# EC-Remoter.net
KiCad netlist of a schematic drawn in Altium Designer
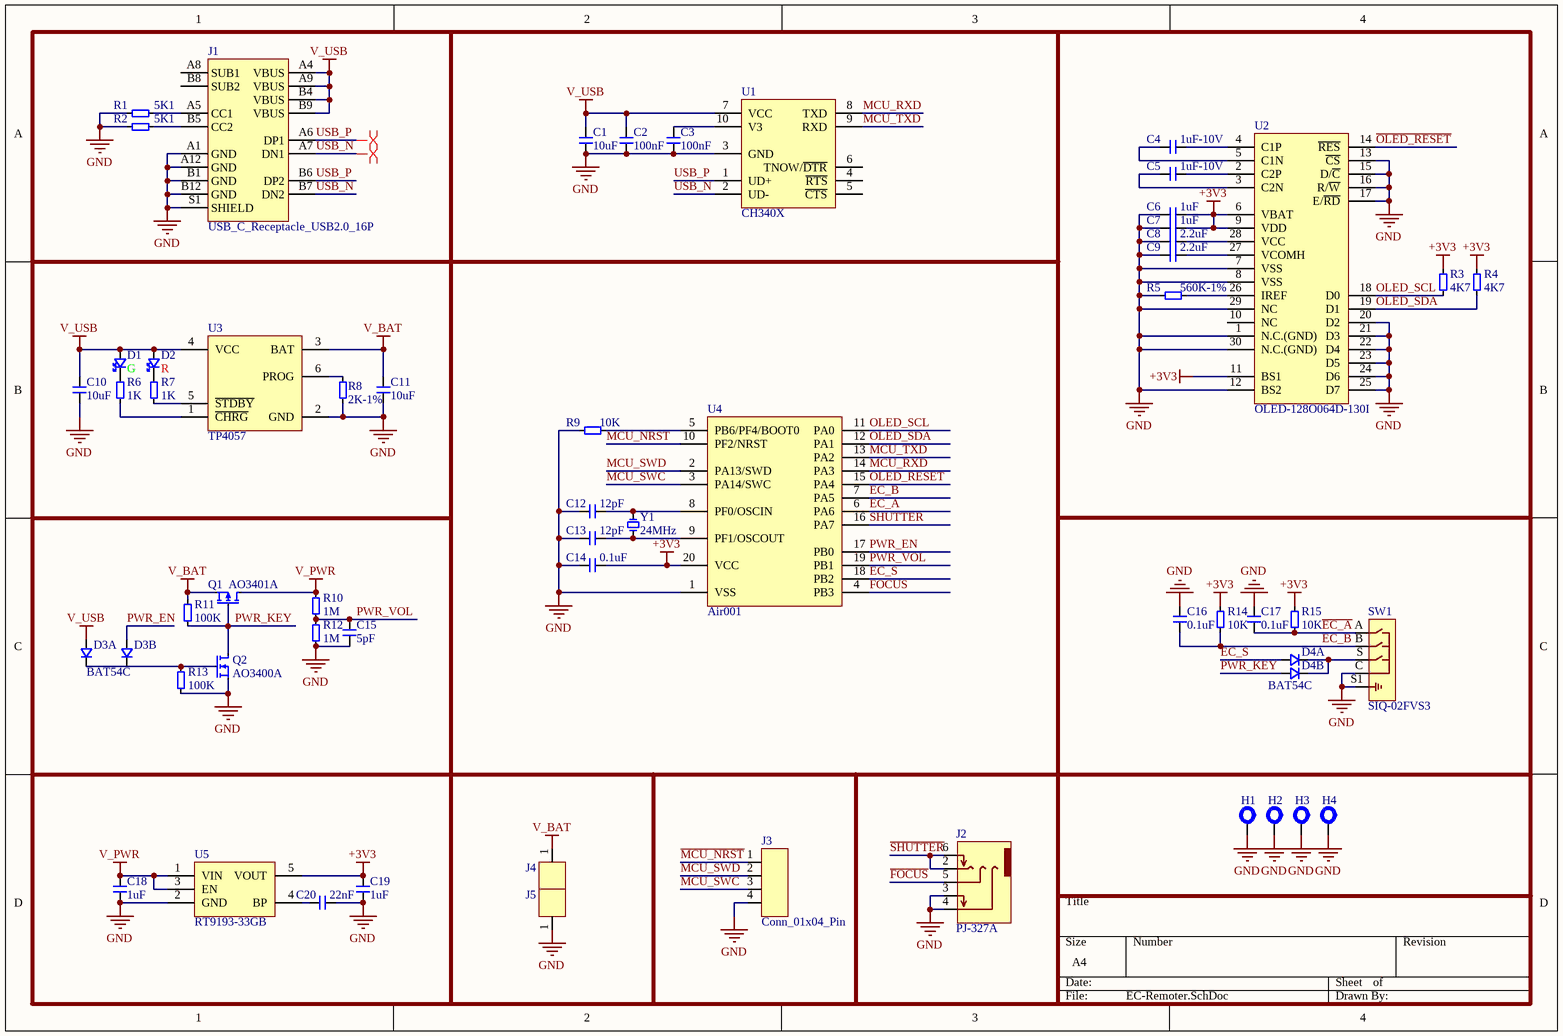
[diagram p0: EC-Remoter.SchDoc]

(export (version "E")
  (design (tool "Eeschema 10.0.6"))
  (components
    (comp (ref "C1")
      (value "10uF")
      (footprint "C_0402_1005Metric")
      (description "Capacitor")
      (libsource (lib "xu-yingjing") (part "C"))
    )
    (comp (ref "C2")
      (value "100nF")
      (footprint "C_0402_1005Metric")
      (description "Capacitor")
      (libsource (lib "xu-yingjing") (part "C"))
    )
    (comp (ref "C3")
      (value "100nF")
      (footprint "C_0402_1005Metric")
      (description "Capacitor")
      (libsource (lib "xu-yingjing") (part "C"))
    )
    (comp (ref "C4")
      (value "1uF-10V")
      (footprint "C_0402_1005Metric")
      (description "Capacitor")
      (libsource (lib "xu-yingjing") (part "C"))
    )
    (comp (ref "C5")
      (value "1uF-10V")
      (footprint "C_0402_1005Metric")
      (description "Capacitor")
      (libsource (lib "xu-yingjing") (part "C"))
    )
    (comp (ref "C6")
      (value "1uF")
      (footprint "C_0402_1005Metric")
      (description "Capacitor")
      (libsource (lib "xu-yingjing") (part "C"))
    )
    (comp (ref "C7")
      (value "1uF")
      (footprint "C_0402_1005Metric")
      (description "Capacitor")
      (libsource (lib "xu-yingjing") (part "C"))
    )
    (comp (ref "C8")
      (value "2.2uF")
      (footprint "C_0402_1005Metric")
      (description "Capacitor")
      (libsource (lib "xu-yingjing") (part "C"))
    )
    (comp (ref "C9")
      (value "2.2uF")
      (footprint "C_0402_1005Metric")
      (description "Capacitor")
      (libsource (lib "xu-yingjing") (part "C"))
    )
    (comp (ref "C10")
      (value "10uF")
      (footprint "C_0402_1005Metric")
      (description "Capacitor")
      (libsource (lib "xu-yingjing") (part "C"))
    )
    (comp (ref "C11")
      (value "10uF")
      (footprint "C_0402_1005Metric")
      (description "Capacitor")
      (libsource (lib "xu-yingjing") (part "C"))
    )
    (comp (ref "C12")
      (value "12pF")
      (footprint "C_0402_1005Metric")
      (description "Capacitor")
      (libsource (lib "xu-yingjing") (part "C"))
    )
    (comp (ref "C13")
      (value "12pF")
      (footprint "C_0402_1005Metric")
      (description "Capacitor")
      (libsource (lib "xu-yingjing") (part "C"))
    )
    (comp (ref "C14")
      (value "0.1uF")
      (footprint "C_0402_1005Metric")
      (description "Capacitor")
      (libsource (lib "xu-yingjing") (part "C"))
    )
    (comp (ref "C15")
      (value "5pF")
      (footprint "C_0402_1005Metric")
      (description "Capacitor")
      (libsource (lib "xu-yingjing") (part "C"))
    )
    (comp (ref "C16")
      (value "0.1uF")
      (footprint "C_0402_1005Metric")
      (description "Capacitor")
      (libsource (lib "xu-yingjing") (part "C"))
    )
    (comp (ref "C17")
      (value "0.1uF")
      (footprint "C_0402_1005Metric")
      (description "Capacitor")
      (libsource (lib "xu-yingjing") (part "C"))
    )
    (comp (ref "C18")
      (value "1uF")
      (footprint "C_0402_1005Metric")
      (description "Capacitor")
      (libsource (lib "xu-yingjing") (part "C"))
    )
    (comp (ref "C19")
      (value "1uF")
      (footprint "C_0402_1005Metric")
      (description "Capacitor")
      (libsource (lib "xu-yingjing") (part "C"))
    )
    (comp (ref "C20")
      (value "22nF")
      (footprint "C_0402_1005Metric")
      (description "Capacitor")
      (libsource (lib "xu-yingjing") (part "C"))
    )
    (comp (ref "D1")
      (value "G")
      (footprint "LED_0603_1608Metric")
      (description "Light emitting diode")
      (libsource (lib "xu-yingjing") (part "LED"))
    )
    (comp (ref "D2")
      (value "R")
      (footprint "LED_0603_1608Metric")
      (description "Light emitting diode")
      (libsource (lib "xu-yingjing") (part "LED"))
    )
    (comp (ref "D3")
      (value "BAT54C")
      (footprint "SOT-23-3")
      (description "dual schottky barrier diode, common cathode")
      (libsource (lib "xu-yingjing") (part "BAT54C"))
    )
    (comp (ref "D4")
      (value "BAT54C")
      (footprint "SOT-23-3")
      (description "dual schottky barrier diode, common cathode")
      (libsource (lib "xu-yingjing") (part "BAT54C"))
    )
    (comp (ref "H1")
      (value "MountingHole_Pad")
      (footprint "MountingHole_2.2mm_M2_Pad_Via")
      (description "Mounting Hole with connection")
      (libsource (lib "xu-yingjing") (part "MountingHole_Pad"))
    )
    (comp (ref "H2")
      (value "MountingHole_Pad")
      (footprint "MountingHole_2.2mm_M2_Pad_Via")
      (description "Mounting Hole with connection")
      (libsource (lib "xu-yingjing") (part "MountingHole_Pad"))
    )
    (comp (ref "H3")
      (value "MountingHole_Pad")
      (footprint "MountingHole_2.2mm_M2_Pad_Via")
      (description "Mounting Hole with connection")
      (libsource (lib "xu-yingjing") (part "MountingHole_Pad"))
    )
    (comp (ref "H4")
      (value "MountingHole_Pad")
      (footprint "MountingHole_2.2mm_M2_Pad_Via")
      (description "Mounting Hole with connection")
      (libsource (lib "xu-yingjing") (part "MountingHole_Pad"))
    )
    (comp (ref "J1")
      (value "USB_C_Receptacle_USB2.0_16P")
      (footprint "USB_C_Receptacle_GCT_USB4105-xx-A_16P_TopMnt_Horizontal")
      (description "USB 2.0-only 16P Type-C Receptacle connector")
      (libsource (lib "xu-yingjing") (part "USB_C_Receptacle_USB2.0_16P"))
    )
    (comp (ref "J2")
      (value "PJ-327A")
      (footprint "Jack_3.5mm_PJ327A_Horizontal")
      (libsource (lib "xu-yingjing") (part "PJ-327A"))
    )
    (comp (ref "J3")
      (value "Conn_01x04_Pin")
      (footprint "PinHeader_1x04_P2.54mm_Vertical")
      (description "Generic connector, single row, 01x04")
      (libsource (lib "xu-yingjing") (part "Conn_01x04_Pin"))
    )
    (comp (ref "J4")
      (value "Conn_01x01_Pin")
      (footprint "TestPoint_Plated_Hole_D1.0mm")
      (description "Generic connector, single row, 01x01")
      (libsource (lib "") (part "Conn_01x01_Pin_1"))
    )
    (comp (ref "J5")
      (value "Conn_01x01_Pin")
      (footprint "TestPoint_Plated_Hole_D1.0mm")
      (description "Generic connector, single row, 01x01")
      (libsource (lib "xu-yingjing") (part "Conn_01x01_Pin"))
    )
    (comp (ref "Q1")
      (value "AO3401A")
      (footprint "SOT-23-3")
      (description "Package_TO_SOT_SMD:SOT-23")
      (libsource (lib "xu-yingjing") (part "AO3401A"))
    )
    (comp (ref "Q2")
      (value "AO3400A")
      (footprint "SOT-23-3")
      (description "30V Vds, 5.7A Id, N-Channel MOSFET, SOT-23")
      (libsource (lib "xu-yingjing") (part "AO3400A"))
    )
    (comp (ref "R1")
      (value "5K1")
      (footprint "R_0402_1005Metric")
      (description "Resistor")
      (libsource (lib "xu-yingjing") (part "R"))
    )
    (comp (ref "R2")
      (value "5K1")
      (footprint "R_0402_1005Metric")
      (description "Resistor")
      (libsource (lib "xu-yingjing") (part "R"))
    )
    (comp (ref "R3")
      (value "4K7")
      (footprint "R_0402_1005Metric")
      (description "Resistor")
      (libsource (lib "xu-yingjing") (part "R"))
    )
    (comp (ref "R4")
      (value "4K7")
      (footprint "R_0402_1005Metric")
      (description "Resistor")
      (libsource (lib "xu-yingjing") (part "R"))
    )
    (comp (ref "R5")
      (value "560K-1%")
      (footprint "R_0402_1005Metric")
      (description "Resistor")
      (libsource (lib "xu-yingjing") (part "R"))
    )
    (comp (ref "R6")
      (value "1K")
      (footprint "R_0402_1005Metric")
      (description "Resistor")
      (libsource (lib "xu-yingjing") (part "R"))
    )
    (comp (ref "R7")
      (value "1K")
      (footprint "R_0402_1005Metric")
      (description "Resistor")
      (libsource (lib "xu-yingjing") (part "R"))
    )
    (comp (ref "R8")
      (value "2K-1%")
      (footprint "R_0402_1005Metric")
      (description "Resistor")
      (libsource (lib "xu-yingjing") (part "R"))
    )
    (comp (ref "R9")
      (value "10K")
      (footprint "R_0402_1005Metric")
      (description "Resistor")
      (libsource (lib "xu-yingjing") (part "R"))
    )
    (comp (ref "R10")
      (value "1M")
      (footprint "R_0402_1005Metric")
      (description "Resistor")
      (libsource (lib "xu-yingjing") (part "R"))
    )
    (comp (ref "R11")
      (value "100K")
      (footprint "R_0402_1005Metric")
      (description "Resistor")
      (libsource (lib "xu-yingjing") (part "R"))
    )
    (comp (ref "R12")
      (value "1M")
      (footprint "R_0402_1005Metric")
      (description "Resistor")
      (libsource (lib "xu-yingjing") (part "R"))
    )
    (comp (ref "R13")
      (value "100K")
      (footprint "R_0402_1005Metric")
      (description "Resistor")
      (libsource (lib "xu-yingjing") (part "R"))
    )
    (comp (ref "R14")
      (value "10K")
      (footprint "R_0402_1005Metric")
      (description "Resistor")
      (libsource (lib "xu-yingjing") (part "R"))
    )
    (comp (ref "R15")
      (value "10K")
      (footprint "R_0402_1005Metric")
      (description "Resistor")
      (libsource (lib "xu-yingjing") (part "R"))
    )
    (comp (ref "SW1")
      (value "SIQ-02FVS3")
      (footprint "SIQ-02FVS3")
      (libsource (lib "xu-yingjing") (part "SIQ-02FVS3"))
    )
    (comp (ref "U1")
      (value "CH340X")
      (footprint "MSOP-10_3x3mm_P0.5mm")
      (description "USB serial converter, 5V-tolerant IO, UART, MSOP-10")
      (libsource (lib "xu-yingjing") (part "CH340X"))
    )
    (comp (ref "U2")
      (value "OLED-128O064D-130I")
      (footprint "OLED-128O064D")
      (description "1.30' OLED display 128x64")
      (libsource (lib "xu-yingjing") (part "OLED-128O064D-130I"))
    )
    (comp (ref "U3")
      (value "TP4057")
      (footprint "SOT-23-6")
      (description "500mA Single-Cell Li-Ion Charger, SOT-23-6")
      (libsource (lib "xu-yingjing") (part "TP4057"))
    )
    (comp (ref "U4")
      (value "Air001")
      (footprint "TSSOP-20_4.4x6.5mm_P0.65mm")
      (description "合宙 Arm Cortex-M0+ MCU, 32KB Flash, 4KB RAM, 48 MHz, 1.7-5.5V, 18 GPIO, TSSOP20")
      (libsource (lib "xu-yingjing") (part "Air001"))
    )
    (comp (ref "U5")
      (value "RT9193-33GB")
      (footprint "SOT-23-5")
      (description "Positive 300mA Low Dropout Regulator")
      (libsource (lib "xu-yingjing") (part "RT9193"))
    )
    (comp (ref "Y1")
      (value "24MHz")
      (footprint "Crystal_SMD_3225-4Pin_3.2x2.5mm")
      (description "Crystal")
      (libsource (lib "xu-yingjing") (part "Crystal"))
    )
  )
  (nets
    (net (code "1") (name "+3V3") (class "Default")
      (node (ref "C14") (pin "2") (pinfunction "2_2") (pintype "passive"))
      (node (ref "C19") (pin "1") (pinfunction "1_1") (pintype "passive"))
      (node (ref "C6") (pin "2") (pinfunction "2_2") (pintype "passive"))
      (node (ref "C7") (pin "2") (pinfunction "2_2") (pintype "passive"))
      (node (ref "R14") (pin "2") (pinfunction "2_2") (pintype "passive"))
      (node (ref "R15") (pin "2") (pinfunction "2_2") (pintype "passive"))
      (node (ref "R3") (pin "1") (pinfunction "1_1") (pintype "passive"))
      (node (ref "R4") (pin "1") (pinfunction "1_1") (pintype "passive"))
      (node (ref "U2") (pin "11") (pinfunction "BS1_11") (pintype "passive"))
      (node (ref "U2") (pin "6") (pinfunction "VBAT_6") (pintype "passive"))
      (node (ref "U2") (pin "9") (pinfunction "VDD_9") (pintype "passive"))
      (node (ref "U4") (pin "20") (pinfunction "VCC_20") (pintype "passive"))
      (node (ref "U5") (pin "5") (pinfunction "VOUT_5") (pintype "passive"))
    )
    (net (code "2") (name "/MCU_RXD") (class "Default")
      (node (ref "U1") (pin "8") (pinfunction "TXD_8") (pintype "passive"))
      (node (ref "U4") (pin "14") (pinfunction "PA3_14") (pintype "passive"))
    )
    (net (code "3") (name "/MCU_SWC") (class "Default")
      (node (ref "J3") (pin "3") (pinfunction "3_3") (pintype "passive"))
      (node (ref "U4") (pin "3") (pinfunction "PA14/SWC_3") (pintype "passive"))
    )
    (net (code "4") (name "/MCU_SWD") (class "Default")
      (node (ref "J3") (pin "2") (pinfunction "2_2") (pintype "passive"))
      (node (ref "U4") (pin "2") (pinfunction "PA13/SWD_2") (pintype "passive"))
    )
    (net (code "5") (name "/MCU_TXD") (class "Default")
      (node (ref "U1") (pin "9") (pinfunction "RXD_9") (pintype "passive"))
      (node (ref "U4") (pin "13") (pinfunction "PA2_13") (pintype "passive"))
    )
    (net (code "6") (name "/OLED_SCL") (class "Default")
      (node (ref "R3") (pin "2") (pinfunction "2_2") (pintype "passive"))
      (node (ref "U2") (pin "18") (pinfunction "D0_18") (pintype "passive"))
      (node (ref "U4") (pin "11") (pinfunction "PA0_11") (pintype "passive"))
    )
    (net (code "7") (name "/OLED_SDA") (class "Default")
      (node (ref "R4") (pin "2") (pinfunction "2_2") (pintype "passive"))
      (node (ref "U2") (pin "19") (pinfunction "D1_19") (pintype "passive"))
      (node (ref "U4") (pin "12") (pinfunction "PA1_12") (pintype "passive"))
    )
    (net (code "8") (name "/PWR_EN") (class "Default")
      (node (ref "D3") (pin "2") (pinfunction "2_2") (pintype "passive"))
      (node (ref "U4") (pin "17") (pinfunction "PB0_17") (pintype "passive"))
    )
    (net (code "9") (name "/PWR_KEY") (class "Default")
      (node (ref "D4") (pin "2") (pinfunction "2_2") (pintype "passive"))
      (node (ref "Q1") (pin "1") (pinfunction "G_1") (pintype "passive"))
      (node (ref "Q2") (pin "3") (pinfunction "D_3") (pintype "passive"))
      (node (ref "R11") (pin "1") (pinfunction "1_1") (pintype "passive"))
    )
    (net (code "10") (name "/PWR_VOL") (class "Default")
      (node (ref "C15") (pin "1") (pinfunction "1_1") (pintype "passive"))
      (node (ref "R10") (pin "2") (pinfunction "2_2") (pintype "passive"))
      (node (ref "R12") (pin "1") (pinfunction "1_1") (pintype "passive"))
      (node (ref "U4") (pin "19") (pinfunction "PB1_19") (pintype "passive"))
    )
    (net (code "11") (name "/USB_N") (class "Default")
      (node (ref "J1") (pin "A7") (pinfunction "DN1_A7") (pintype "passive"))
      (node (ref "J1") (pin "B7") (pinfunction "DN2_B7") (pintype "passive"))
      (node (ref "U1") (pin "2") (pinfunction "UD-_2") (pintype "passive"))
    )
    (net (code "12") (name "/USB_P") (class "Default")
      (node (ref "J1") (pin "A6") (pinfunction "DP1_A6") (pintype "passive"))
      (node (ref "J1") (pin "B6") (pinfunction "DP2_B6") (pintype "passive"))
      (node (ref "U1") (pin "1") (pinfunction "UD+_1") (pintype "passive"))
    )
    (net (code "13") (name "/~{EC_A}") (class "Default")
      (node (ref "C17") (pin "1") (pinfunction "1_1") (pintype "passive"))
      (node (ref "R15") (pin "1") (pinfunction "1_1") (pintype "passive"))
      (node (ref "SW1") (pin "A") (pinfunction "A_A") (pintype "passive"))
      (node (ref "U4") (pin "6") (pinfunction "PA6_6") (pintype "passive"))
    )
    (net (code "14") (name "/~{EC_B}") (class "Default")
      (node (ref "C16") (pin "1") (pinfunction "1_1") (pintype "passive"))
      (node (ref "R14") (pin "1") (pinfunction "1_1") (pintype "passive"))
      (node (ref "SW1") (pin "B") (pinfunction "B_B") (pintype "passive"))
      (node (ref "U4") (pin "7") (pinfunction "PA5_7") (pintype "passive"))
    )
    (net (code "15") (name "/~{EC_S}") (class "Default")
      (node (ref "D4") (pin "1") (pinfunction "1_1") (pintype "passive"))
      (node (ref "U4") (pin "18") (pinfunction "PB2_18") (pintype "passive"))
    )
    (net (code "16") (name "/~{FOCUS}") (class "Default")
      (node (ref "J2") (pin "5") (pinfunction "5_5") (pintype "passive"))
      (node (ref "U4") (pin "4") (pinfunction "PB3_4") (pintype "passive"))
    )
    (net (code "17") (name "/~{MCU_NRST}") (class "Default")
      (node (ref "J3") (pin "1") (pinfunction "1_1") (pintype "passive"))
      (node (ref "U4") (pin "10") (pinfunction "PF2/NRST_10") (pintype "passive"))
    )
    (net (code "18") (name "/~{OLED_RESET}") (class "Default")
      (node (ref "U2") (pin "14") (pinfunction "~{RES}_14") (pintype "passive"))
      (node (ref "U4") (pin "15") (pinfunction "PA4_15") (pintype "passive"))
    )
    (net (code "19") (name "/~{SHUTTER}") (class "Default")
      (node (ref "J2") (pin "2") (pinfunction "2_2") (pintype "passive"))
      (node (ref "J2") (pin "6") (pinfunction "6_6") (pintype "passive"))
      (node (ref "U4") (pin "16") (pinfunction "PA7_16") (pintype "passive"))
    )
    (net (code "20") (name "GND") (class "Default")
      (node (ref "C1") (pin "2") (pinfunction "2_2") (pintype "passive"))
      (node (ref "C10") (pin "2") (pinfunction "2_2") (pintype "passive"))
      (node (ref "C11") (pin "2") (pinfunction "2_2") (pintype "passive"))
      (node (ref "C12") (pin "1") (pinfunction "1_1") (pintype "passive"))
      (node (ref "C13") (pin "1") (pinfunction "1_1") (pintype "passive"))
      (node (ref "C14") (pin "1") (pinfunction "1_1") (pintype "passive"))
      (node (ref "C15") (pin "2") (pinfunction "2_2") (pintype "passive"))
      (node (ref "C16") (pin "2") (pinfunction "2_2") (pintype "passive"))
      (node (ref "C17") (pin "2") (pinfunction "2_2") (pintype "passive"))
      (node (ref "C18") (pin "2") (pinfunction "2_2") (pintype "passive"))
      (node (ref "C19") (pin "2") (pinfunction "2_2") (pintype "passive"))
      (node (ref "C2") (pin "2") (pinfunction "2_2") (pintype "passive"))
      (node (ref "C20") (pin "2") (pinfunction "2_2") (pintype "passive"))
      (node (ref "C3") (pin "2") (pinfunction "2_2") (pintype "passive"))
      (node (ref "C6") (pin "1") (pinfunction "1_1") (pintype "passive"))
      (node (ref "C7") (pin "1") (pinfunction "1_1") (pintype "passive"))
      (node (ref "C8") (pin "1") (pinfunction "1_1") (pintype "passive"))
      (node (ref "C9") (pin "1") (pinfunction "1_1") (pintype "passive"))
      (node (ref "H1") (pin "1") (pinfunction "1_1") (pintype "passive"))
      (node (ref "H2") (pin "1") (pinfunction "1_1") (pintype "passive"))
      (node (ref "H3") (pin "1") (pinfunction "1_1") (pintype "passive"))
      (node (ref "H4") (pin "1") (pinfunction "1_1") (pintype "passive"))
      (node (ref "J1") (pin "A1") (pinfunction "GND_A1") (pintype "passive"))
      (node (ref "J1") (pin "A12") (pinfunction "GND_A12") (pintype "passive"))
      (node (ref "J1") (pin "B1") (pinfunction "GND_B1") (pintype "passive"))
      (node (ref "J1") (pin "B12") (pinfunction "GND_B12") (pintype "passive"))
      (node (ref "J1") (pin "S1") (pinfunction "SHIELD_S1") (pintype "passive"))
      (node (ref "J2") (pin "3") (pinfunction "3_3") (pintype "passive"))
      (node (ref "J2") (pin "4") (pinfunction "4_4") (pintype "passive"))
      (node (ref "J3") (pin "4") (pinfunction "4_4") (pintype "passive"))
      (node (ref "J4") (pin "1") (pinfunction "1_1") (pintype "passive"))
      (node (ref "Q2") (pin "2") (pinfunction "S_2") (pintype "passive"))
      (node (ref "R1") (pin "1") (pinfunction "1_1") (pintype "passive"))
      (node (ref "R12") (pin "2") (pinfunction "2_2") (pintype "passive"))
      (node (ref "R13") (pin "2") (pinfunction "2_2") (pintype "passive"))
      (node (ref "R2") (pin "1") (pinfunction "1_1") (pintype "passive"))
      (node (ref "R5") (pin "1") (pinfunction "1_1") (pintype "passive"))
      (node (ref "R8") (pin "2") (pinfunction "2_2") (pintype "passive"))
      (node (ref "R9") (pin "1") (pinfunction "1_1") (pintype "passive"))
      (node (ref "SW1") (pin "C") (pinfunction "C_C") (pintype "passive"))
      (node (ref "SW1") (pin "S1") (pinfunction "SHIELD_S1") (pintype "passive"))
      (node (ref "U1") (pin "3") (pinfunction "GND_3") (pintype "passive"))
      (node (ref "U2") (pin "1") (pinfunction "N.C.(GND)_1") (pintype "passive"))
      (node (ref "U2") (pin "12") (pinfunction "BS2_12") (pintype "passive"))
      (node (ref "U2") (pin "13") (pinfunction "~{CS}_13") (pintype "passive"))
      (node (ref "U2") (pin "15") (pinfunction "D/~{C}_15") (pintype "passive"))
      (node (ref "U2") (pin "16") (pinfunction "R/~{W}_16") (pintype "passive"))
      (node (ref "U2") (pin "17") (pinfunction "E/~{RD}_17") (pintype "passive"))
      (node (ref "U2") (pin "20") (pinfunction "D2_20") (pintype "passive"))
      (node (ref "U2") (pin "21") (pinfunction "D3_21") (pintype "passive"))
      (node (ref "U2") (pin "22") (pinfunction "D4_22") (pintype "passive"))
      (node (ref "U2") (pin "23") (pinfunction "D5_23") (pintype "passive"))
      (node (ref "U2") (pin "24") (pinfunction "D6_24") (pintype "passive"))
      (node (ref "U2") (pin "25") (pinfunction "D7_25") (pintype "passive"))
      (node (ref "U2") (pin "29") (pinfunction "NC_29") (pintype "passive"))
      (node (ref "U2") (pin "30") (pinfunction "N.C.(GND)_30") (pintype "passive"))
      (node (ref "U2") (pin "7") (pinfunction "VSS_7") (pintype "passive"))
      (node (ref "U2") (pin "8") (pinfunction "VSS_8") (pintype "passive"))
      (node (ref "U3") (pin "2") (pinfunction "GND_2") (pintype "passive"))
      (node (ref "U4") (pin "1") (pinfunction "VSS_1") (pintype "passive"))
      (node (ref "U5") (pin "2") (pinfunction "GND_2") (pintype "passive"))
    )
    (net (code "21") (name "Net-(D1-K)") (class "Default")
      (node (ref "D1") (pin "1") (pinfunction "K_1") (pintype "passive"))
      (node (ref "R6") (pin "1") (pinfunction "1_1") (pintype "passive"))
    )
    (net (code "22") (name "Net-(D2-K)") (class "Default")
      (node (ref "D2") (pin "1") (pinfunction "K_1") (pintype "passive"))
      (node (ref "R7") (pin "1") (pinfunction "1_1") (pintype "passive"))
    )
    (net (code "23") (name "Net-(D4-Pad3)") (class "Default")
      (node (ref "D4") (pin "3") (pinfunction "3_3") (pintype "passive"))
      (node (ref "SW1") (pin "S") (pinfunction "S_S") (pintype "passive"))
    )
    (net (code "24") (name "Net-(J1-CC1)") (class "Default")
      (node (ref "J1") (pin "A5") (pinfunction "CC1_A5") (pintype "passive"))
      (node (ref "R1") (pin "2") (pinfunction "2_2") (pintype "passive"))
    )
    (net (code "25") (name "Net-(J1-CC2)") (class "Default")
      (node (ref "J1") (pin "B5") (pinfunction "CC2_B5") (pintype "passive"))
      (node (ref "R2") (pin "2") (pinfunction "2_2") (pintype "passive"))
    )
    (net (code "26") (name "Net-(Q2-G)") (class "Default")
      (node (ref "D3") (pin "3") (pinfunction "3_3") (pintype "passive"))
      (node (ref "Q2") (pin "1") (pinfunction "G_1") (pintype "passive"))
      (node (ref "R13") (pin "1") (pinfunction "1_1") (pintype "passive"))
    )
    (net (code "27") (name "Net-(U1-V3)") (class "Default")
      (node (ref "C3") (pin "1") (pinfunction "1_1") (pintype "passive"))
      (node (ref "U1") (pin "10") (pinfunction "V3_10") (pintype "passive"))
    )
    (net (code "28") (name "Net-(U2-C1N)") (class "Default")
      (node (ref "C4") (pin "1") (pinfunction "1_1") (pintype "passive"))
      (node (ref "U2") (pin "5") (pinfunction "C1N_5") (pintype "passive"))
    )
    (net (code "29") (name "Net-(U2-C1P)") (class "Default")
      (node (ref "C4") (pin "2") (pinfunction "2_2") (pintype "passive"))
      (node (ref "U2") (pin "4") (pinfunction "C1P_4") (pintype "passive"))
    )
    (net (code "30") (name "Net-(U2-C2N)") (class "Default")
      (node (ref "C5") (pin "1") (pinfunction "1_1") (pintype "passive"))
      (node (ref "U2") (pin "3") (pinfunction "C2N_3") (pintype "passive"))
    )
    (net (code "31") (name "Net-(U2-C2P)") (class "Default")
      (node (ref "C5") (pin "2") (pinfunction "2_2") (pintype "passive"))
      (node (ref "U2") (pin "2") (pinfunction "C2P_2") (pintype "passive"))
    )
    (net (code "32") (name "Net-(U2-IREF)") (class "Default")
      (node (ref "R5") (pin "2") (pinfunction "2_2") (pintype "passive"))
      (node (ref "U2") (pin "26") (pinfunction "IREF_26") (pintype "passive"))
    )
    (net (code "33") (name "Net-(U2-VCC)") (class "Default")
      (node (ref "C8") (pin "2") (pinfunction "2_2") (pintype "passive"))
      (node (ref "U2") (pin "28") (pinfunction "VCC_28") (pintype "passive"))
    )
    (net (code "34") (name "Net-(U2-VCOMH)") (class "Default")
      (node (ref "C9") (pin "2") (pinfunction "2_2") (pintype "passive"))
      (node (ref "U2") (pin "27") (pinfunction "VCOMH_27") (pintype "passive"))
    )
    (net (code "35") (name "Net-(U3-PROG)") (class "Default")
      (node (ref "R8") (pin "1") (pinfunction "1_1") (pintype "passive"))
      (node (ref "U3") (pin "6") (pinfunction "PROG_6") (pintype "passive"))
    )
    (net (code "36") (name "Net-(U3-~{CHRG})") (class "Default")
      (node (ref "R6") (pin "2") (pinfunction "2_2") (pintype "passive"))
      (node (ref "U3") (pin "1") (pinfunction "~{CHRG}_1") (pintype "passive"))
    )
    (net (code "37") (name "Net-(U3-~{STDBY})") (class "Default")
      (node (ref "R7") (pin "2") (pinfunction "2_2") (pintype "passive"))
      (node (ref "U3") (pin "5") (pinfunction "~{STDBY}_5") (pintype "passive"))
    )
    (net (code "38") (name "Net-(U4-PB6{slash}PF4{slash}BOOT0)") (class "Default")
      (node (ref "R9") (pin "2") (pinfunction "2_2") (pintype "passive"))
      (node (ref "U4") (pin "5") (pinfunction "PB6/PF4/BOOT0_5") (pintype "passive"))
    )
    (net (code "39") (name "Net-(U4-PF0{slash}OSCIN)") (class "Default")
      (node (ref "C12") (pin "2") (pinfunction "2_2") (pintype "passive"))
      (node (ref "U4") (pin "8") (pinfunction "PF0/OSCIN_8") (pintype "passive"))
      (node (ref "Y1") (pin "1") (pinfunction "1_1") (pintype "passive"))
    )
    (net (code "40") (name "Net-(U4-PF1{slash}OSCOUT)") (class "Default")
      (node (ref "C13") (pin "2") (pinfunction "2_2") (pintype "passive"))
      (node (ref "U4") (pin "9") (pinfunction "PF1/OSCOUT_9") (pintype "passive"))
      (node (ref "Y1") (pin "2") (pinfunction "2_2") (pintype "passive"))
    )
    (net (code "41") (name "Net-(U5-BP)") (class "Default")
      (node (ref "C20") (pin "1") (pinfunction "1_1") (pintype "passive"))
      (node (ref "U5") (pin "4") (pinfunction "BP_4") (pintype "passive"))
    )
    (net (code "42") (name "V_BAT") (class "Default")
      (node (ref "C11") (pin "1") (pinfunction "1_1") (pintype "passive"))
      (node (ref "J5") (pin "1") (pinfunction "1_1") (pintype "passive"))
      (node (ref "Q1") (pin "2") (pinfunction "S_2") (pintype "passive"))
      (node (ref "R11") (pin "2") (pinfunction "2_2") (pintype "passive"))
      (node (ref "U3") (pin "3") (pinfunction "BAT_3") (pintype "passive"))
    )
    (net (code "43") (name "V_PWR") (class "Default")
      (node (ref "C18") (pin "1") (pinfunction "1_1") (pintype "passive"))
      (node (ref "Q1") (pin "3") (pinfunction "D_3") (pintype "passive"))
      (node (ref "R10") (pin "1") (pinfunction "1_1") (pintype "passive"))
      (node (ref "U5") (pin "1") (pinfunction "VIN_1") (pintype "passive"))
      (node (ref "U5") (pin "3") (pinfunction "EN_3") (pintype "passive"))
    )
    (net (code "44") (name "V_USB") (class "Default")
      (node (ref "C1") (pin "1") (pinfunction "1_1") (pintype "passive"))
      (node (ref "C10") (pin "1") (pinfunction "1_1") (pintype "passive"))
      (node (ref "C2") (pin "1") (pinfunction "1_1") (pintype "passive"))
      (node (ref "D1") (pin "2") (pinfunction "A_2") (pintype "passive"))
      (node (ref "D2") (pin "2") (pinfunction "A_2") (pintype "passive"))
      (node (ref "D3") (pin "1") (pinfunction "1_1") (pintype "passive"))
      (node (ref "J1") (pin "A4") (pinfunction "VBUS_A4") (pintype "passive"))
      (node (ref "J1") (pin "A9") (pinfunction "VBUS_A9") (pintype "passive"))
      (node (ref "J1") (pin "B4") (pinfunction "VBUS_B4") (pintype "passive"))
      (node (ref "J1") (pin "B9") (pinfunction "VBUS_B9") (pintype "passive"))
      (node (ref "U1") (pin "7") (pinfunction "VCC_7") (pintype "passive"))
      (node (ref "U3") (pin "4") (pinfunction "VCC_4") (pintype "passive"))
    )
    (net (code "45") (name "unconnected-(J1-SUB1-PadA8)") (class "Default")
      (node (ref "J1") (pin "A8") (pinfunction "SUB1_A8") (pintype "passive"))
    )
    (net (code "46") (name "unconnected-(J1-SUB2-PadB8)") (class "Default")
      (node (ref "J1") (pin "B8") (pinfunction "SUB2_B8") (pintype "passive"))
    )
    (net (code "47") (name "unconnected-(U1-TNOW{slash}~{DTR}-Pad6)") (class "Default")
      (node (ref "U1") (pin "6") (pinfunction "TNOW/~{DTR}_6") (pintype "passive"))
    )
    (net (code "48") (name "unconnected-(U1-~{CTS}-Pad5)") (class "Default")
      (node (ref "U1") (pin "5") (pinfunction "~{CTS}_5") (pintype "passive"))
    )
    (net (code "49") (name "unconnected-(U1-~{RTS}-Pad4)") (class "Default")
      (node (ref "U1") (pin "4") (pinfunction "~{RTS}_4") (pintype "passive"))
    )
    (net (code "50") (name "unconnected-(U2-NC-Pad10)") (class "Default")
      (node (ref "U2") (pin "10") (pinfunction "NC_10") (pintype "passive"))
    )
  )
)
